# Controller-Modul_v1.net
KiCad netlist of a schematic drawn in EAGLE
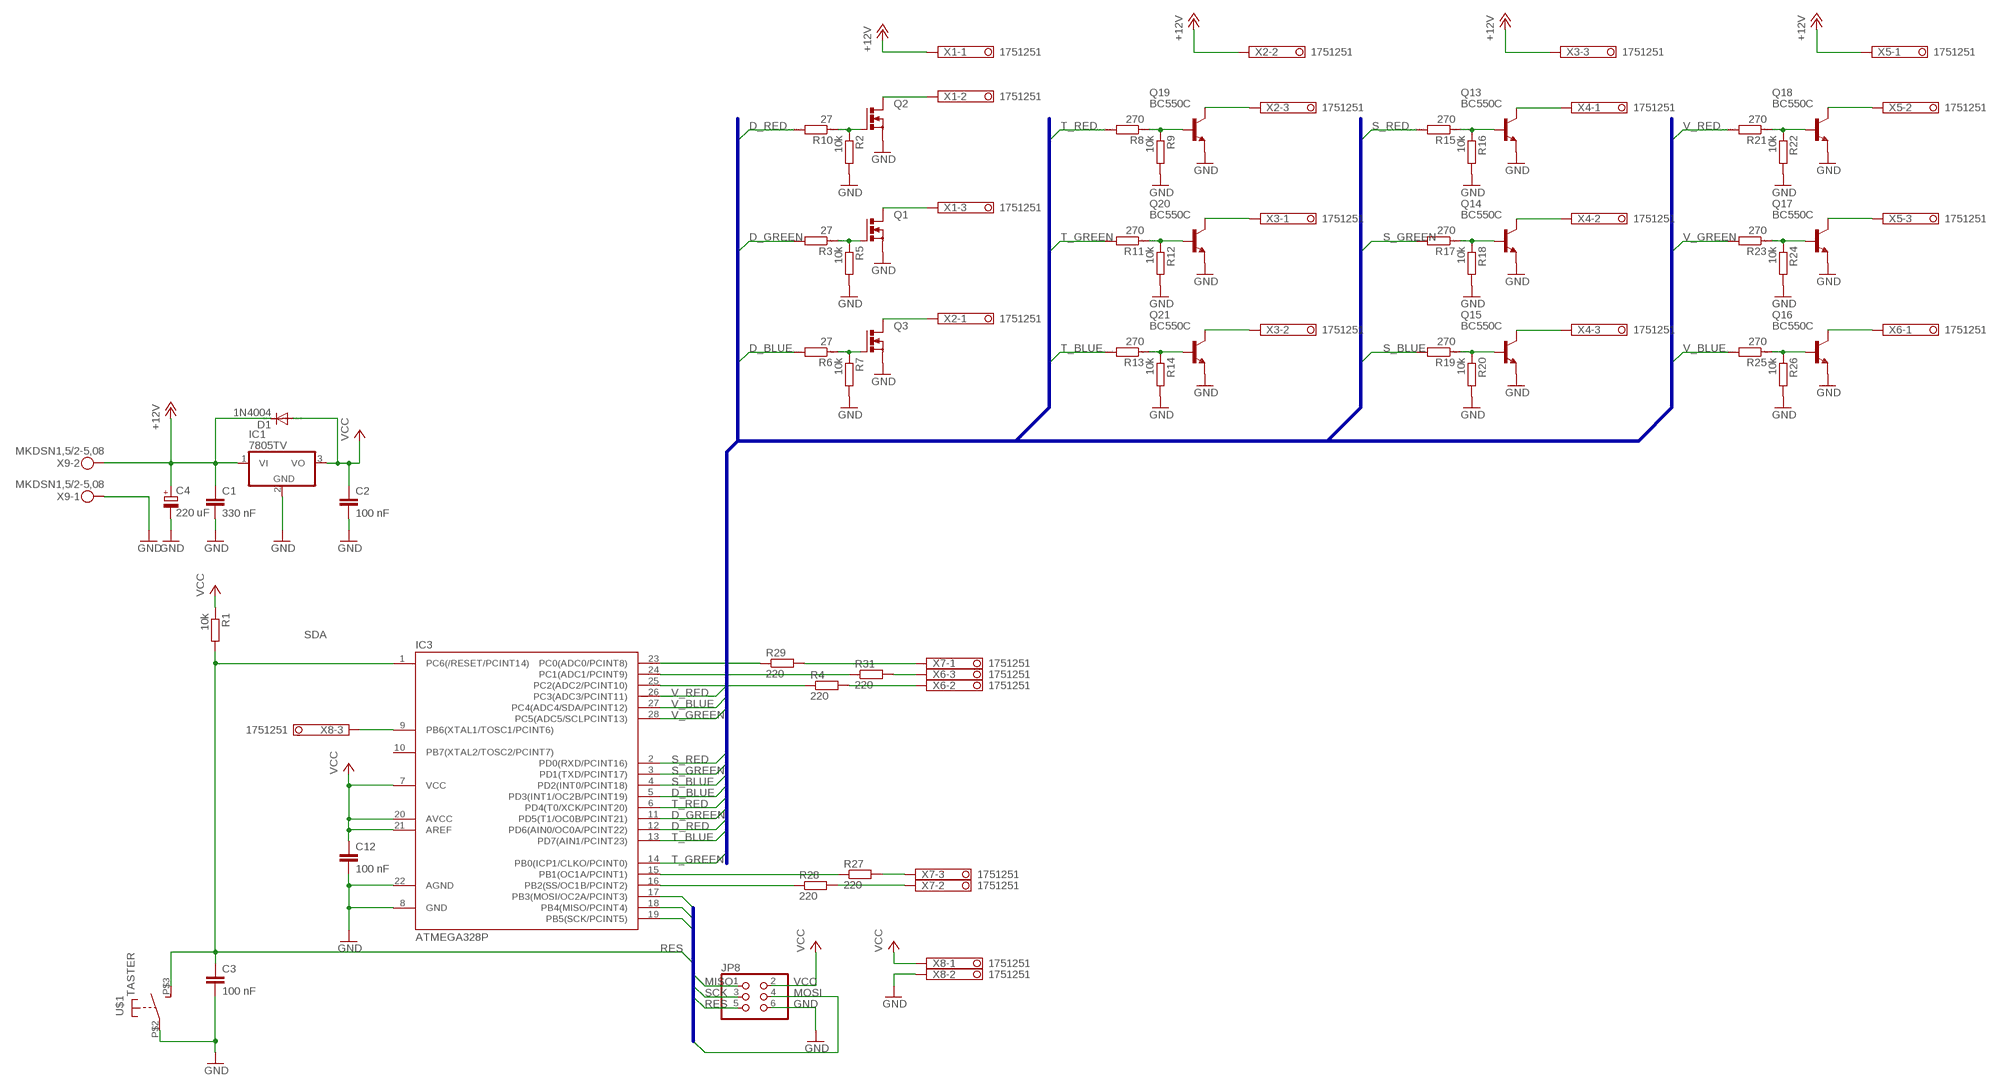
[diagram p0: schematic, sheet 1]

(export (version "E")
  (design (tool "Eeschema 10.0.6"))
  (components
    (comp (ref "C1")
      (value "330 nF")
      (footprint "eagle-import:C1206")
      (libsource (lib "eagle-import") (part "C-EUC1206"))
    )
    (comp (ref "C2")
      (value "100 nF")
      (footprint "eagle-import:C0603")
      (libsource (lib "eagle-import") (part "C-EUC0603"))
    )
    (comp (ref "C3")
      (value "100 nF")
      (footprint "eagle-import:C0603")
      (libsource (lib "eagle-import") (part "C-EUC0603"))
    )
    (comp (ref "C4")
      (value "220 uF")
      (footprint "eagle-import:E3,5-8")
      (libsource (lib "eagle-import") (part "CPOL-EUE3.5-8"))
    )
    (comp (ref "C12")
      (value "100 nF")
      (footprint "eagle-import:C0603")
      (libsource (lib "eagle-import") (part "C-EUC0603"))
    )
    (comp (ref "D1")
      (value "1N4004")
      (footprint "eagle-import:DO41-10")
      (libsource (lib "eagle-import") (part "1N4004"))
    )
    (comp (ref "IC1")
      (value "7805TV")
      (footprint "eagle-import:TO220V")
      (libsource (lib "eagle-import") (part "78TV05"))
    )
    (comp (ref "IC3")
      (value "ATMEGA328P")
      (footprint "eagle-import:DIL28-3")
      (libsource (lib "eagle-import") (part "MEGA48/88/168-PU"))
    )
    (comp (ref "JP8")
      (value "PINHD-2X3")
      (footprint "eagle-import:2X03")
      (libsource (lib "eagle-import") (part "PINHD-2X3"))
    )
    (comp (ref "Q1")
      (value "PMOSFET_NTO220BV")
      (footprint "eagle-import:TO220BV")
      (libsource (lib "eagle-import") (part "PMOSFET_NTO220BV"))
    )
    (comp (ref "Q2")
      (value "PMOSFET_NTO220BV")
      (footprint "eagle-import:TO220BV")
      (libsource (lib "eagle-import") (part "PMOSFET_NTO220BV"))
    )
    (comp (ref "Q3")
      (value "PMOSFET_NTO220BV")
      (footprint "eagle-import:TO220BV")
      (libsource (lib "eagle-import") (part "PMOSFET_NTO220BV"))
    )
    (comp (ref "Q13")
      (value "BC550C")
      (footprint "eagle-import:TO92-EBC")
      (libsource (lib "eagle-import") (part "BC550C"))
    )
    (comp (ref "Q14")
      (value "BC550C")
      (footprint "eagle-import:TO92-EBC")
      (libsource (lib "eagle-import") (part "BC550C"))
    )
    (comp (ref "Q15")
      (value "BC550C")
      (footprint "eagle-import:TO92-EBC")
      (libsource (lib "eagle-import") (part "BC550C"))
    )
    (comp (ref "Q16")
      (value "BC550C")
      (footprint "eagle-import:TO92-EBC")
      (libsource (lib "eagle-import") (part "BC550C"))
    )
    (comp (ref "Q17")
      (value "BC550C")
      (footprint "eagle-import:TO92-EBC")
      (libsource (lib "eagle-import") (part "BC550C"))
    )
    (comp (ref "Q18")
      (value "BC550C")
      (footprint "eagle-import:TO92-EBC")
      (libsource (lib "eagle-import") (part "BC550C"))
    )
    (comp (ref "Q19")
      (value "BC550C")
      (footprint "eagle-import:TO92-EBC")
      (libsource (lib "eagle-import") (part "BC550C"))
    )
    (comp (ref "Q20")
      (value "BC550C")
      (footprint "eagle-import:TO92-EBC")
      (libsource (lib "eagle-import") (part "BC550C"))
    )
    (comp (ref "Q21")
      (value "BC550C")
      (footprint "eagle-import:TO92-EBC")
      (libsource (lib "eagle-import") (part "BC550C"))
    )
    (comp (ref "R1")
      (value "10k")
      (footprint "eagle-import:R1206")
      (libsource (lib "eagle-import") (part "R-EU_R1206"))
    )
    (comp (ref "R2")
      (value "10k")
      (footprint "eagle-import:R1206")
      (libsource (lib "eagle-import") (part "R-EU_R1206"))
    )
    (comp (ref "R3")
      (value "27")
      (footprint "eagle-import:R1206")
      (libsource (lib "eagle-import") (part "RR1206"))
    )
    (comp (ref "R4")
      (value "220")
      (footprint "eagle-import:R1206")
      (libsource (lib "eagle-import") (part "R-EU_R1206"))
    )
    (comp (ref "R5")
      (value "10k")
      (footprint "eagle-import:R1206")
      (libsource (lib "eagle-import") (part "R-EU_R1206"))
    )
    (comp (ref "R6")
      (value "27")
      (footprint "eagle-import:R1206")
      (libsource (lib "eagle-import") (part "RR1206"))
    )
    (comp (ref "R7")
      (value "10k")
      (footprint "eagle-import:R1206")
      (libsource (lib "eagle-import") (part "R-EU_R1206"))
    )
    (comp (ref "R8")
      (value "270")
      (footprint "eagle-import:R1206")
      (libsource (lib "eagle-import") (part "RR1206"))
    )
    (comp (ref "R9")
      (value "10k")
      (footprint "eagle-import:R1206")
      (libsource (lib "eagle-import") (part "R-EU_R1206"))
    )
    (comp (ref "R10")
      (value "27")
      (footprint "eagle-import:R1206")
      (libsource (lib "eagle-import") (part "RR1206"))
    )
    (comp (ref "R11")
      (value "270")
      (footprint "eagle-import:R1206")
      (libsource (lib "eagle-import") (part "RR1206"))
    )
    (comp (ref "R12")
      (value "10k")
      (footprint "eagle-import:R1206")
      (libsource (lib "eagle-import") (part "R-EU_R1206"))
    )
    (comp (ref "R13")
      (value "270")
      (footprint "eagle-import:R1206")
      (libsource (lib "eagle-import") (part "RR1206"))
    )
    (comp (ref "R14")
      (value "10k")
      (footprint "eagle-import:R1206")
      (libsource (lib "eagle-import") (part "R-EU_R1206"))
    )
    (comp (ref "R15")
      (value "270")
      (footprint "eagle-import:R1206")
      (libsource (lib "eagle-import") (part "RR1206"))
    )
    (comp (ref "R16")
      (value "10k")
      (footprint "eagle-import:R1206")
      (libsource (lib "eagle-import") (part "R-EU_R1206"))
    )
    (comp (ref "R17")
      (value "270")
      (footprint "eagle-import:R1206")
      (libsource (lib "eagle-import") (part "RR1206"))
    )
    (comp (ref "R18")
      (value "10k")
      (footprint "eagle-import:R1206")
      (libsource (lib "eagle-import") (part "R-EU_R1206"))
    )
    (comp (ref "R19")
      (value "270")
      (footprint "eagle-import:R1206")
      (libsource (lib "eagle-import") (part "RR1206"))
    )
    (comp (ref "R20")
      (value "10k")
      (footprint "eagle-import:R1206")
      (libsource (lib "eagle-import") (part "R-EU_R1206"))
    )
    (comp (ref "R21")
      (value "270")
      (footprint "eagle-import:R1206")
      (libsource (lib "eagle-import") (part "RR1206"))
    )
    (comp (ref "R22")
      (value "10k")
      (footprint "eagle-import:R1206")
      (libsource (lib "eagle-import") (part "R-EU_R1206"))
    )
    (comp (ref "R23")
      (value "270")
      (footprint "eagle-import:R1206")
      (libsource (lib "eagle-import") (part "RR1206"))
    )
    (comp (ref "R24")
      (value "10k")
      (footprint "eagle-import:R1206")
      (libsource (lib "eagle-import") (part "R-EU_R1206"))
    )
    (comp (ref "R25")
      (value "270")
      (footprint "eagle-import:R1206")
      (libsource (lib "eagle-import") (part "RR1206"))
    )
    (comp (ref "R26")
      (value "10k")
      (footprint "eagle-import:R1206")
      (libsource (lib "eagle-import") (part "R-EU_R1206"))
    )
    (comp (ref "R27")
      (value "220")
      (footprint "eagle-import:R1206")
      (libsource (lib "eagle-import") (part "R-EU_R1206"))
    )
    (comp (ref "R28")
      (value "220")
      (footprint "eagle-import:R1206")
      (libsource (lib "eagle-import") (part "R-EU_R1206"))
    )
    (comp (ref "R29")
      (value "220")
      (footprint "eagle-import:R1206")
      (libsource (lib "eagle-import") (part "R-EU_R1206"))
    )
    (comp (ref "R31")
      (value "220")
      (footprint "eagle-import:R1206")
      (libsource (lib "eagle-import") (part "R-EU_R1206"))
    )
    (comp (ref "U$1")
      (value "TASTER")
      (footprint "eagle-import:NAMAE-JTP-1130")
      (libsource (lib "eagle-import") (part "TASTER"))
    )
    (comp (ref "X1")
      (value "1751251")
      (footprint "eagle-import:1751251")
      (libsource (lib "eagle-import") (part "1751251"))
    )
    (comp (ref "X2")
      (value "1751251")
      (footprint "eagle-import:1751251")
      (libsource (lib "eagle-import") (part "1751251"))
    )
    (comp (ref "X3")
      (value "1751251")
      (footprint "eagle-import:1751251")
      (libsource (lib "eagle-import") (part "1751251"))
    )
    (comp (ref "X4")
      (value "1751251")
      (footprint "eagle-import:1751251")
      (libsource (lib "eagle-import") (part "1751251"))
    )
    (comp (ref "X5")
      (value "1751251")
      (footprint "eagle-import:1751251")
      (libsource (lib "eagle-import") (part "1751251"))
    )
    (comp (ref "X6")
      (value "1751251")
      (footprint "eagle-import:1751251")
      (libsource (lib "eagle-import") (part "1751251"))
    )
    (comp (ref "X7")
      (value "1751251")
      (footprint "eagle-import:1751251")
      (libsource (lib "eagle-import") (part "1751251"))
    )
    (comp (ref "X8")
      (value "1751251")
      (footprint "eagle-import:1751251")
      (libsource (lib "eagle-import") (part "1751251"))
    )
    (comp (ref "X9")
      (value "MKDSN1,5/2-5,08")
      (footprint "eagle-import:MKDSN1,5_2-5,08")
      (libsource (lib "eagle-import") (part "MKDSN1,5/2-5,08"))
    )
  )
  (nets
    (net (code "1") (name "+12V") (class "Default")
      (node (ref "C1") (pin "1") (pinfunction "1_1") (pintype "passive"))
      (node (ref "C4") (pin "+") (pinfunction "+_+") (pintype "passive"))
      (node (ref "D1") (pin "C") (pinfunction "C_C") (pintype "passive"))
      (node (ref "IC1") (pin "1") (pinfunction "VI_1") (pintype "input"))
      (node (ref "X1") (pin "1") (pinfunction "K_1") (pintype "passive"))
      (node (ref "X2") (pin "2") (pinfunction "K_2") (pintype "passive"))
      (node (ref "X3") (pin "3") (pinfunction "K_3") (pintype "passive"))
      (node (ref "X5") (pin "1") (pinfunction "K_1") (pintype "passive"))
      (node (ref "X9") (pin "2") (pinfunction "KL_2") (pintype "passive"))
    )
    (net (code "2") (name "/D_BLUE") (class "Default")
      (node (ref "IC3") (pin "5") (pinfunction "PD3(INT1/OC2B/PCINT19)_5") (pintype "bidirectional"))
      (node (ref "R6") (pin "2") (pinfunction "2_2") (pintype "passive"))
    )
    (net (code "3") (name "/D_GREEN") (class "Default")
      (node (ref "IC3") (pin "11") (pinfunction "PD5(T1/OC0B/PCINT21)_11") (pintype "bidirectional"))
      (node (ref "R3") (pin "2") (pinfunction "2_2") (pintype "passive"))
    )
    (net (code "4") (name "/D_RED") (class "Default")
      (node (ref "IC3") (pin "12") (pinfunction "PD6(AIN0/OC0A/PCINT22)_12") (pintype "bidirectional"))
      (node (ref "R10") (pin "2") (pinfunction "2_2") (pintype "passive"))
    )
    (net (code "5") (name "/MISO") (class "Default")
      (node (ref "IC3") (pin "18") (pinfunction "PB4(MISO/PCINT4)_18") (pintype "bidirectional"))
      (node (ref "JP8") (pin "1") (pinfunction "1_1") (pintype "passive"))
    )
    (net (code "6") (name "/MOSI") (class "Default")
      (node (ref "IC3") (pin "17") (pinfunction "PB3(MOSI/OC2A/PCINT3)_17") (pintype "bidirectional"))
      (node (ref "JP8") (pin "4") (pinfunction "4_4") (pintype "passive"))
    )
    (net (code "7") (name "/RES") (class "Default")
      (node (ref "C3") (pin "1") (pinfunction "1_1") (pintype "passive"))
      (node (ref "IC3") (pin "1") (pinfunction "PC6(/RESET/PCINT14)_1") (pintype "bidirectional"))
      (node (ref "JP8") (pin "5") (pinfunction "5_5") (pintype "passive"))
      (node (ref "R1") (pin "2") (pinfunction "2_2") (pintype "passive"))
      (node (ref "U$1") (pin "P$3") (pinfunction "S_P$3") (pintype "passive"))
    )
    (net (code "8") (name "/SCK") (class "Default")
      (node (ref "IC3") (pin "19") (pinfunction "PB5(SCK/PCINT5)_19") (pintype "bidirectional"))
      (node (ref "JP8") (pin "3") (pinfunction "3_3") (pintype "passive"))
    )
    (net (code "9") (name "/S_BLUE") (class "Default")
      (node (ref "IC3") (pin "4") (pinfunction "PD2(INT0/PCINT18)_4") (pintype "bidirectional"))
      (node (ref "R19") (pin "2") (pinfunction "2_2") (pintype "passive"))
    )
    (net (code "10") (name "/S_GREEN") (class "Default")
      (node (ref "IC3") (pin "3") (pinfunction "PD1(TXD/PCINT17)_3") (pintype "bidirectional"))
      (node (ref "R17") (pin "2") (pinfunction "2_2") (pintype "passive"))
    )
    (net (code "11") (name "/S_RED") (class "Default")
      (node (ref "IC3") (pin "2") (pinfunction "PD0(RXD/PCINT16)_2") (pintype "bidirectional"))
      (node (ref "R15") (pin "2") (pinfunction "2_2") (pintype "passive"))
    )
    (net (code "12") (name "/T_BLUE") (class "Default")
      (node (ref "IC3") (pin "13") (pinfunction "PD7(AIN1/PCINT23)_13") (pintype "bidirectional"))
      (node (ref "R13") (pin "2") (pinfunction "2_2") (pintype "passive"))
    )
    (net (code "13") (name "/T_GREEN") (class "Default")
      (node (ref "IC3") (pin "14") (pinfunction "PB0(ICP1/CLKO/PCINT0)_14") (pintype "bidirectional"))
      (node (ref "R11") (pin "2") (pinfunction "2_2") (pintype "passive"))
    )
    (net (code "14") (name "/T_RED") (class "Default")
      (node (ref "IC3") (pin "6") (pinfunction "PD4(T0/XCK/PCINT20)_6") (pintype "bidirectional"))
      (node (ref "R8") (pin "2") (pinfunction "2_2") (pintype "passive"))
    )
    (net (code "15") (name "/V_BLUE") (class "Default")
      (node (ref "IC3") (pin "27") (pinfunction "PC4(ADC4/SDA/PCINT12)_27") (pintype "bidirectional"))
      (node (ref "R25") (pin "2") (pinfunction "2_2") (pintype "passive"))
    )
    (net (code "16") (name "/V_GREEN") (class "Default")
      (node (ref "IC3") (pin "28") (pinfunction "PC5(ADC5/SCLPCINT13)_28") (pintype "bidirectional"))
      (node (ref "R23") (pin "2") (pinfunction "2_2") (pintype "passive"))
    )
    (net (code "17") (name "/V_RED") (class "Default")
      (node (ref "IC3") (pin "26") (pinfunction "PC3(ADC3/PCINT11)_26") (pintype "bidirectional"))
      (node (ref "R21") (pin "2") (pinfunction "2_2") (pintype "passive"))
    )
    (net (code "18") (name "GND") (class "Default")
      (node (ref "C1") (pin "2") (pinfunction "2_2") (pintype "passive"))
      (node (ref "C12") (pin "2") (pinfunction "2_2") (pintype "passive"))
      (node (ref "C2") (pin "2") (pinfunction "2_2") (pintype "passive"))
      (node (ref "C3") (pin "2") (pinfunction "2_2") (pintype "passive"))
      (node (ref "C4") (pin "-") (pinfunction "-_-") (pintype "passive"))
      (node (ref "IC1") (pin "2") (pinfunction "GND_2") (pintype "passive"))
      (node (ref "IC3") (pin "22") (pinfunction "AGND_22") (pintype "power_in"))
      (node (ref "IC3") (pin "8") (pinfunction "GND_8") (pintype "power_in"))
      (node (ref "JP8") (pin "6") (pinfunction "6_6") (pintype "passive"))
      (node (ref "Q1") (pin "S") (pinfunction "S_S") (pintype "passive"))
      (node (ref "Q13") (pin "E") (pinfunction "E_E") (pintype "passive"))
      (node (ref "Q14") (pin "E") (pinfunction "E_E") (pintype "passive"))
      (node (ref "Q15") (pin "E") (pinfunction "E_E") (pintype "passive"))
      (node (ref "Q16") (pin "E") (pinfunction "E_E") (pintype "passive"))
      (node (ref "Q17") (pin "E") (pinfunction "E_E") (pintype "passive"))
      (node (ref "Q18") (pin "E") (pinfunction "E_E") (pintype "passive"))
      (node (ref "Q19") (pin "E") (pinfunction "E_E") (pintype "passive"))
      (node (ref "Q2") (pin "S") (pinfunction "S_S") (pintype "passive"))
      (node (ref "Q20") (pin "E") (pinfunction "E_E") (pintype "passive"))
      (node (ref "Q21") (pin "E") (pinfunction "E_E") (pintype "passive"))
      (node (ref "Q3") (pin "S") (pinfunction "S_S") (pintype "passive"))
      (node (ref "R12") (pin "2") (pinfunction "2_2") (pintype "passive"))
      (node (ref "R14") (pin "2") (pinfunction "2_2") (pintype "passive"))
      (node (ref "R16") (pin "2") (pinfunction "2_2") (pintype "passive"))
      (node (ref "R18") (pin "2") (pinfunction "2_2") (pintype "passive"))
      (node (ref "R2") (pin "2") (pinfunction "2_2") (pintype "passive"))
      (node (ref "R20") (pin "2") (pinfunction "2_2") (pintype "passive"))
      (node (ref "R22") (pin "2") (pinfunction "2_2") (pintype "passive"))
      (node (ref "R24") (pin "2") (pinfunction "2_2") (pintype "passive"))
      (node (ref "R26") (pin "2") (pinfunction "2_2") (pintype "passive"))
      (node (ref "R5") (pin "2") (pinfunction "2_2") (pintype "passive"))
      (node (ref "R7") (pin "2") (pinfunction "2_2") (pintype "passive"))
      (node (ref "R9") (pin "2") (pinfunction "2_2") (pintype "passive"))
      (node (ref "U$1") (pin "P$2") (pinfunction "P_P$2") (pintype "passive"))
      (node (ref "X8") (pin "2") (pinfunction "K_2") (pintype "passive"))
      (node (ref "X9") (pin "1") (pinfunction "KL_1") (pintype "passive"))
    )
    (net (code "19") (name "Net-(IC3-PB1(OC1A{slash}PCINT1))") (class "Default")
      (node (ref "IC3") (pin "15") (pinfunction "PB1(OC1A/PCINT1)_15") (pintype "bidirectional"))
      (node (ref "R27") (pin "1") (pinfunction "1_1") (pintype "passive"))
    )
    (net (code "20") (name "Net-(IC3-PB2(SS{slash}OC1B{slash}PCINT2))") (class "Default")
      (node (ref "IC3") (pin "16") (pinfunction "PB2(SS/OC1B/PCINT2)_16") (pintype "bidirectional"))
      (node (ref "R28") (pin "1") (pinfunction "1_1") (pintype "passive"))
    )
    (net (code "21") (name "Net-(IC3-PB6(XTAL1{slash}TOSC1{slash}PCINT6))") (class "Default")
      (node (ref "IC3") (pin "9") (pinfunction "PB6(XTAL1/TOSC1/PCINT6)_9") (pintype "bidirectional"))
      (node (ref "X8") (pin "3") (pinfunction "K_3") (pintype "passive"))
    )
    (net (code "22") (name "Net-(IC3-PC0(ADC0{slash}PCINT8))") (class "Default")
      (node (ref "IC3") (pin "23") (pinfunction "PC0(ADC0/PCINT8)_23") (pintype "bidirectional"))
      (node (ref "R29") (pin "1") (pinfunction "1_1") (pintype "passive"))
    )
    (net (code "23") (name "Net-(IC3-PC1(ADC1{slash}PCINT9))") (class "Default")
      (node (ref "IC3") (pin "24") (pinfunction "PC1(ADC1/PCINT9)_24") (pintype "bidirectional"))
      (node (ref "R31") (pin "1") (pinfunction "1_1") (pintype "passive"))
    )
    (net (code "24") (name "Net-(IC3-PC2(ADC2{slash}PCINT10))") (class "Default")
      (node (ref "IC3") (pin "25") (pinfunction "PC2(ADC2/PCINT10)_25") (pintype "bidirectional"))
      (node (ref "R4") (pin "1") (pinfunction "1_1") (pintype "passive"))
    )
    (net (code "25") (name "Net-(Q1-PadG)") (class "Default")
      (node (ref "Q1") (pin "G") (pinfunction "G_G") (pintype "passive"))
      (node (ref "R3") (pin "1") (pinfunction "1_1") (pintype "passive"))
      (node (ref "R5") (pin "1") (pinfunction "1_1") (pintype "passive"))
    )
    (net (code "26") (name "Net-(Q2-PadG)") (class "Default")
      (node (ref "Q2") (pin "G") (pinfunction "G_G") (pintype "passive"))
      (node (ref "R10") (pin "1") (pinfunction "1_1") (pintype "passive"))
      (node (ref "R2") (pin "1") (pinfunction "1_1") (pintype "passive"))
    )
    (net (code "27") (name "Net-(Q3-PadG)") (class "Default")
      (node (ref "Q3") (pin "G") (pinfunction "G_G") (pintype "passive"))
      (node (ref "R6") (pin "1") (pinfunction "1_1") (pintype "passive"))
      (node (ref "R7") (pin "1") (pinfunction "1_1") (pintype "passive"))
    )
    (net (code "28") (name "Net-(Q13-PadB)") (class "Default")
      (node (ref "Q13") (pin "B") (pinfunction "B_B") (pintype "passive"))
      (node (ref "R15") (pin "1") (pinfunction "1_1") (pintype "passive"))
      (node (ref "R16") (pin "1") (pinfunction "1_1") (pintype "passive"))
    )
    (net (code "29") (name "Net-(Q14-PadB)") (class "Default")
      (node (ref "Q14") (pin "B") (pinfunction "B_B") (pintype "passive"))
      (node (ref "R17") (pin "1") (pinfunction "1_1") (pintype "passive"))
      (node (ref "R18") (pin "1") (pinfunction "1_1") (pintype "passive"))
    )
    (net (code "30") (name "Net-(Q15-PadB)") (class "Default")
      (node (ref "Q15") (pin "B") (pinfunction "B_B") (pintype "passive"))
      (node (ref "R19") (pin "1") (pinfunction "1_1") (pintype "passive"))
      (node (ref "R20") (pin "1") (pinfunction "1_1") (pintype "passive"))
    )
    (net (code "31") (name "Net-(Q16-PadB)") (class "Default")
      (node (ref "Q16") (pin "B") (pinfunction "B_B") (pintype "passive"))
      (node (ref "R25") (pin "1") (pinfunction "1_1") (pintype "passive"))
      (node (ref "R26") (pin "1") (pinfunction "1_1") (pintype "passive"))
    )
    (net (code "32") (name "Net-(Q17-PadB)") (class "Default")
      (node (ref "Q17") (pin "B") (pinfunction "B_B") (pintype "passive"))
      (node (ref "R23") (pin "1") (pinfunction "1_1") (pintype "passive"))
      (node (ref "R24") (pin "1") (pinfunction "1_1") (pintype "passive"))
    )
    (net (code "33") (name "Net-(Q18-PadB)") (class "Default")
      (node (ref "Q18") (pin "B") (pinfunction "B_B") (pintype "passive"))
      (node (ref "R21") (pin "1") (pinfunction "1_1") (pintype "passive"))
      (node (ref "R22") (pin "1") (pinfunction "1_1") (pintype "passive"))
    )
    (net (code "34") (name "Net-(Q19-PadB)") (class "Default")
      (node (ref "Q19") (pin "B") (pinfunction "B_B") (pintype "passive"))
      (node (ref "R8") (pin "1") (pinfunction "1_1") (pintype "passive"))
      (node (ref "R9") (pin "1") (pinfunction "1_1") (pintype "passive"))
    )
    (net (code "35") (name "Net-(Q20-PadB)") (class "Default")
      (node (ref "Q20") (pin "B") (pinfunction "B_B") (pintype "passive"))
      (node (ref "R11") (pin "1") (pinfunction "1_1") (pintype "passive"))
      (node (ref "R12") (pin "1") (pinfunction "1_1") (pintype "passive"))
    )
    (net (code "36") (name "Net-(Q21-PadB)") (class "Default")
      (node (ref "Q21") (pin "B") (pinfunction "B_B") (pintype "passive"))
      (node (ref "R13") (pin "1") (pinfunction "1_1") (pintype "passive"))
      (node (ref "R14") (pin "1") (pinfunction "1_1") (pintype "passive"))
    )
    (net (code "37") (name "Net-(X1B-K)") (class "Default")
      (node (ref "Q2") (pin "D") (pinfunction "D_D") (pintype "passive"))
      (node (ref "X1") (pin "2") (pinfunction "K_2") (pintype "passive"))
    )
    (net (code "38") (name "Net-(X1C-K)") (class "Default")
      (node (ref "Q1") (pin "D") (pinfunction "D_D") (pintype "passive"))
      (node (ref "X1") (pin "3") (pinfunction "K_3") (pintype "passive"))
    )
    (net (code "39") (name "Net-(X2A-K)") (class "Default")
      (node (ref "Q3") (pin "D") (pinfunction "D_D") (pintype "passive"))
      (node (ref "X2") (pin "1") (pinfunction "K_1") (pintype "passive"))
    )
    (net (code "40") (name "Net-(X2C-K)") (class "Default")
      (node (ref "Q19") (pin "C") (pinfunction "C_C") (pintype "passive"))
      (node (ref "X2") (pin "3") (pinfunction "K_3") (pintype "passive"))
    )
    (net (code "41") (name "Net-(X3A-K)") (class "Default")
      (node (ref "Q20") (pin "C") (pinfunction "C_C") (pintype "passive"))
      (node (ref "X3") (pin "1") (pinfunction "K_1") (pintype "passive"))
    )
    (net (code "42") (name "Net-(X3B-K)") (class "Default")
      (node (ref "Q21") (pin "C") (pinfunction "C_C") (pintype "passive"))
      (node (ref "X3") (pin "2") (pinfunction "K_2") (pintype "passive"))
    )
    (net (code "43") (name "Net-(X4A-K)") (class "Default")
      (node (ref "Q13") (pin "C") (pinfunction "C_C") (pintype "passive"))
      (node (ref "X4") (pin "1") (pinfunction "K_1") (pintype "passive"))
    )
    (net (code "44") (name "Net-(X4B-K)") (class "Default")
      (node (ref "Q14") (pin "C") (pinfunction "C_C") (pintype "passive"))
      (node (ref "X4") (pin "2") (pinfunction "K_2") (pintype "passive"))
    )
    (net (code "45") (name "Net-(X4C-K)") (class "Default")
      (node (ref "Q15") (pin "C") (pinfunction "C_C") (pintype "passive"))
      (node (ref "X4") (pin "3") (pinfunction "K_3") (pintype "passive"))
    )
    (net (code "46") (name "Net-(X5B-K)") (class "Default")
      (node (ref "Q18") (pin "C") (pinfunction "C_C") (pintype "passive"))
      (node (ref "X5") (pin "2") (pinfunction "K_2") (pintype "passive"))
    )
    (net (code "47") (name "Net-(X5C-K)") (class "Default")
      (node (ref "Q17") (pin "C") (pinfunction "C_C") (pintype "passive"))
      (node (ref "X5") (pin "3") (pinfunction "K_3") (pintype "passive"))
    )
    (net (code "48") (name "Net-(X6A-K)") (class "Default")
      (node (ref "Q16") (pin "C") (pinfunction "C_C") (pintype "passive"))
      (node (ref "X6") (pin "1") (pinfunction "K_1") (pintype "passive"))
    )
    (net (code "49") (name "Net-(X6B-K)") (class "Default")
      (node (ref "R4") (pin "2") (pinfunction "2_2") (pintype "passive"))
      (node (ref "X6") (pin "2") (pinfunction "K_2") (pintype "passive"))
    )
    (net (code "50") (name "Net-(X6C-K)") (class "Default")
      (node (ref "R31") (pin "2") (pinfunction "2_2") (pintype "passive"))
      (node (ref "X6") (pin "3") (pinfunction "K_3") (pintype "passive"))
    )
    (net (code "51") (name "Net-(X7A-K)") (class "Default")
      (node (ref "R29") (pin "2") (pinfunction "2_2") (pintype "passive"))
      (node (ref "X7") (pin "1") (pinfunction "K_1") (pintype "passive"))
    )
    (net (code "52") (name "Net-(X7B-K)") (class "Default")
      (node (ref "R28") (pin "2") (pinfunction "2_2") (pintype "passive"))
      (node (ref "X7") (pin "2") (pinfunction "K_2") (pintype "passive"))
    )
    (net (code "53") (name "Net-(X7C-K)") (class "Default")
      (node (ref "R27") (pin "2") (pinfunction "2_2") (pintype "passive"))
      (node (ref "X7") (pin "3") (pinfunction "K_3") (pintype "passive"))
    )
    (net (code "54") (name "VCC") (class "Default")
      (node (ref "C12") (pin "1") (pinfunction "1_1") (pintype "passive"))
      (node (ref "C2") (pin "1") (pinfunction "1_1") (pintype "passive"))
      (node (ref "D1") (pin "A") (pinfunction "A_A") (pintype "passive"))
      (node (ref "IC1") (pin "3") (pinfunction "VO_3") (pintype "passive"))
      (node (ref "IC3") (pin "20") (pinfunction "AVCC_20") (pintype "passive"))
      (node (ref "IC3") (pin "21") (pinfunction "AREF_21") (pintype "passive"))
      (node (ref "IC3") (pin "7") (pinfunction "VCC_7") (pintype "power_in"))
      (node (ref "JP8") (pin "2") (pinfunction "2_2") (pintype "passive"))
      (node (ref "R1") (pin "1") (pinfunction "1_1") (pintype "passive"))
      (node (ref "X8") (pin "1") (pinfunction "K_1") (pintype "passive"))
    )
    (net (code "55") (name "unconnected-(IC3-PB7(XTAL2{slash}TOSC2{slash}PCINT7)-Pad10)") (class "Default")
      (node (ref "IC3") (pin "10") (pinfunction "PB7(XTAL2/TOSC2/PCINT7)_10") (pintype "bidirectional"))
    )
  )
)
